# optic_fiber_rx.net
KiCad netlist of a schematic drawn in Altium Designer
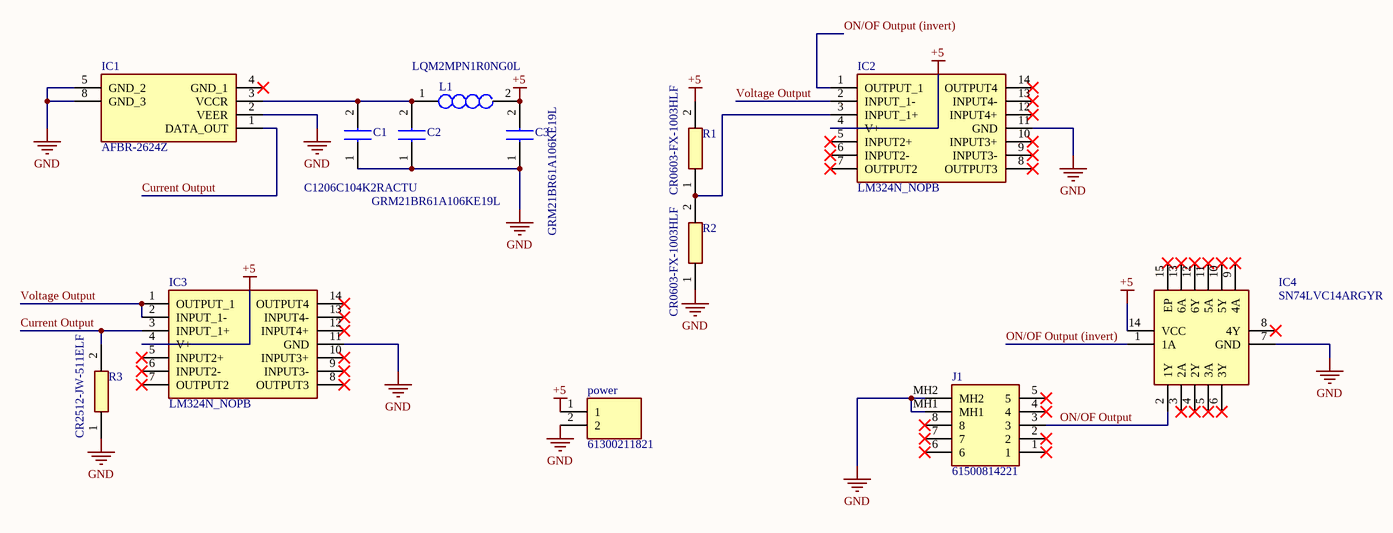
[diagram p0: optic_fiber_rx.SchDoc]

(export (version "E")
  (design (tool "Eeschema 10.0.6"))
  (components
    (comp (ref "C1")
      (value "C1206C104K2RACTU")
      (footprint "optic_fiber:C1206")
      (description "Capacitor")
      (fields (field (name "MOUSER PART NUMBER") "80-C1206C104K2R"))
      (libsource (lib "*") (part "C1206C104K2RACTU"))
    )
    (comp (ref "C2")
      (value "GRM21BR61A106KE19L")
      (footprint "optic_fiber:CAPC2012X145N")
      (description "Capacitor")
      (fields (field (name "MOUSER PART NUMBER") "81-GRM21BR61A106KE19"))
      (libsource (lib "*") (part "GRM21BR61A106KE19L"))
    )
    (comp (ref "C3")
      (value "GRM21BR61A106KE19L")
      (footprint "optic_fiber:CAPC2012X145N")
      (description "Capacitor")
      (fields (field (name "MOUSER PART NUMBER") "81-GRM21BR61A106KE19"))
      (libsource (lib "*") (part "GRM21BR61A106KE19L"))
    )
    (comp (ref "IC1")
      (value "AFBR-2624Z")
      (footprint "optic_fiber:AFBR2624Z")
      (description "Integrated Circuit")
      (fields (field (name "MOUSER PART NUMBER") "630-AFBR-2624Z"))
      (libsource (lib "*") (part "AFBR-2624Z"))
    )
    (comp (ref "IC2")
      (value "LM324N_NOPB")
      (footprint "optic_fiber:DIP794W56P254L1905H533Q14N")
      (description "Integrated Circuit")
      (fields
        (field (name "MANUFACTURER_PART_NUMBER") "LM324N/NOPB")
        (field (name "MOUSER PART NUMBER") "926-LM324N/NOPB")
      )
      (libsource (lib "*") (part "LM324N_NOPB"))
    )
    (comp (ref "IC3")
      (value "LM324N_NOPB")
      (footprint "optic_fiber:DIP794W56P254L1905H533Q14N")
      (description "Integrated Circuit")
      (fields
        (field (name "MANUFACTURER_PART_NUMBER") "LM324N/NOPB")
        (field (name "MOUSER PART NUMBER") "926-LM324N/NOPB")
      )
      (libsource (lib "*") (part "LM324N_NOPB"))
    )
    (comp (ref "IC4")
      (value "SN74LVC14ARGYR")
      (footprint "optic_fiber:RGY-(S-PVQFN-N14)")
      (description "Integrated Circuit")
      (fields (field (name "MOUSER PART NUMBER") "595-SN74LVC14ARGYR"))
      (libsource (lib "*") (part "SN74LVC14ARGYR"))
    )
    (comp (ref "J1")
      (value "61500814221")
      (footprint "optic_fiber:61500814221")
      (description "Connector")
      (fields (field (name "MOUSER PART NUMBER") "710-61500814221"))
      (libsource (lib "*") (part "61500814221"))
    )
    (comp (ref "L1")
      (value "LQM2MPN1R0NG0L")
      (footprint "optic_fiber:LQM2MPN1R0NG0L")
      (description "Inductor")
      (fields (field (name "MOUSER PART NUMBER") "81-LQM2MPN1R0NG0L"))
      (libsource (lib "*") (part "LQM2MPN1R0NG0L"))
    )
    (comp (ref "power")
      (value "61300211821")
      (footprint "optic_fiber:61300211821")
      (description "Connector")
      (libsource (lib "*") (part "61300211821"))
    )
    (comp (ref "R1")
      (value "CR0603-FX-1003HLF")
      (footprint "optic_fiber:RESC1608X55N")
      (description "Resistor")
      (fields (field (name "MOUSER PART NUMBER") "652-CR0603-FX1003HLF"))
      (libsource (lib "*") (part "CR0603-FX-1003HLF"))
    )
    (comp (ref "R2")
      (value "CR0603-FX-1003HLF")
      (footprint "optic_fiber:RESC1608X55N")
      (description "Resistor")
      (fields (field (name "MOUSER PART NUMBER") "652-CR0603-FX1003HLF"))
      (libsource (lib "*") (part "CR0603-FX-1003HLF"))
    )
    (comp (ref "R3")
      (value "CR2512-JW-511ELF")
      (footprint "optic_fiber:RESC6331X75N")
      (description "Resistor")
      (fields (field (name "MOUSER PART NUMBER") "652-CR2512-JW-511ELF"))
      (libsource (lib "*") (part "CR2512-JW-511ELF"))
    )
  )
  (nets
    (net (code "1") (name "+5") (class "Default")
      (node (ref "C3") (pin "2") (pinfunction "2_2") (pintype "passive"))
      (node (ref "IC2") (pin "4") (pinfunction "V+_4") (pintype "passive"))
      (node (ref "IC3") (pin "4") (pinfunction "V+_4") (pintype "passive"))
      (node (ref "IC4") (pin "14") (pinfunction "VCC_14") (pintype "passive"))
      (node (ref "L1") (pin "2") (pinfunction "2_2") (pintype "passive"))
      (node (ref "R1") (pin "2") (pinfunction "2_2") (pintype "passive"))
      (node (ref "power") (pin "1") (pinfunction "1_1") (pintype "passive"))
    )
    (net (code "2") (name "/Current Output") (class "Default")
      (node (ref "IC1") (pin "1") (pinfunction "DATA_OUT_1") (pintype "passive"))
      (node (ref "IC3") (pin "3") (pinfunction "INPUT_1+_3") (pintype "passive"))
      (node (ref "R3") (pin "2") (pinfunction "2_2") (pintype "passive"))
    )
    (net (code "3") (name "/ON{slash}OF Output") (class "Default")
      (node (ref "IC4") (pin "2") (pinfunction "1Y_2") (pintype "passive"))
      (node (ref "J1") (pin "3") (pinfunction "3_3") (pintype "passive"))
    )
    (net (code "4") (name "/ON{slash}OF Output (invert)") (class "Default")
      (node (ref "IC2") (pin "1") (pinfunction "OUTPUT_1_1") (pintype "passive"))
      (node (ref "IC4") (pin "1") (pinfunction "1A_1") (pintype "passive"))
    )
    (net (code "5") (name "/Voltage Output") (class "Default")
      (node (ref "IC2") (pin "2") (pinfunction "INPUT_1-_2") (pintype "passive"))
      (node (ref "IC3") (pin "1") (pinfunction "OUTPUT_1_1") (pintype "passive"))
      (node (ref "IC3") (pin "2") (pinfunction "INPUT_1-_2") (pintype "passive"))
    )
    (net (code "6") (name "GND") (class "Default")
      (node (ref "C1") (pin "1") (pinfunction "1_1") (pintype "passive"))
      (node (ref "C2") (pin "1") (pinfunction "1_1") (pintype "passive"))
      (node (ref "C3") (pin "1") (pinfunction "1_1") (pintype "passive"))
      (node (ref "IC1") (pin "2") (pinfunction "VEER_2") (pintype "passive"))
      (node (ref "IC1") (pin "5") (pinfunction "GND_2_5") (pintype "passive"))
      (node (ref "IC1") (pin "8") (pinfunction "GND_3_8") (pintype "passive"))
      (node (ref "IC2") (pin "11") (pinfunction "GND_11") (pintype "passive"))
      (node (ref "IC3") (pin "11") (pinfunction "GND_11") (pintype "passive"))
      (node (ref "IC4") (pin "7") (pinfunction "GND_7") (pintype "passive"))
      (node (ref "J1") (pin "MH1") (pinfunction "MH1_MH1") (pintype "passive"))
      (node (ref "J1") (pin "MH2") (pinfunction "MH2_MH2") (pintype "passive"))
      (node (ref "R2") (pin "1") (pinfunction "1_1") (pintype "passive"))
      (node (ref "R3") (pin "1") (pinfunction "1_1") (pintype "passive"))
      (node (ref "power") (pin "2") (pinfunction "2_2") (pintype "passive"))
    )
    (net (code "7") (name "Net-(IC1-VCCR)") (class "Default")
      (node (ref "C1") (pin "2") (pinfunction "2_2") (pintype "passive"))
      (node (ref "C2") (pin "2") (pinfunction "2_2") (pintype "passive"))
      (node (ref "IC1") (pin "3") (pinfunction "VCCR_3") (pintype "passive"))
      (node (ref "L1") (pin "1") (pinfunction "1_1") (pintype "passive"))
    )
    (net (code "8") (name "Net-(IC2-INPUT_1+)") (class "Default")
      (node (ref "IC2") (pin "3") (pinfunction "INPUT_1+_3") (pintype "passive"))
      (node (ref "R1") (pin "1") (pinfunction "1_1") (pintype "passive"))
      (node (ref "R2") (pin "2") (pinfunction "2_2") (pintype "passive"))
    )
    (net (code "9") (name "unconnected-(IC1-GND_1-Pad4)") (class "Default")
      (node (ref "IC1") (pin "4") (pinfunction "GND_1_4") (pintype "passive+no_connect"))
    )
    (net (code "10") (name "unconnected-(IC2-INPUT2+-Pad5)") (class "Default")
      (node (ref "IC2") (pin "5") (pinfunction "INPUT2+_5") (pintype "passive+no_connect"))
    )
    (net (code "11") (name "unconnected-(IC2-INPUT2--Pad6)") (class "Default")
      (node (ref "IC2") (pin "6") (pinfunction "INPUT2-_6") (pintype "passive+no_connect"))
    )
    (net (code "12") (name "unconnected-(IC2-INPUT3+-Pad10)") (class "Default")
      (node (ref "IC2") (pin "10") (pinfunction "INPUT3+_10") (pintype "passive+no_connect"))
    )
    (net (code "13") (name "unconnected-(IC2-INPUT3--Pad9)") (class "Default")
      (node (ref "IC2") (pin "9") (pinfunction "INPUT3-_9") (pintype "passive+no_connect"))
    )
    (net (code "14") (name "unconnected-(IC2-INPUT4+-Pad12)") (class "Default")
      (node (ref "IC2") (pin "12") (pinfunction "INPUT4+_12") (pintype "passive+no_connect"))
    )
    (net (code "15") (name "unconnected-(IC2-INPUT4--Pad13)") (class "Default")
      (node (ref "IC2") (pin "13") (pinfunction "INPUT4-_13") (pintype "passive+no_connect"))
    )
    (net (code "16") (name "unconnected-(IC2-OUTPUT2-Pad7)") (class "Default")
      (node (ref "IC2") (pin "7") (pinfunction "OUTPUT2_7") (pintype "passive+no_connect"))
    )
    (net (code "17") (name "unconnected-(IC2-OUTPUT3-Pad8)") (class "Default")
      (node (ref "IC2") (pin "8") (pinfunction "OUTPUT3_8") (pintype "passive+no_connect"))
    )
    (net (code "18") (name "unconnected-(IC2-OUTPUT4-Pad14)") (class "Default")
      (node (ref "IC2") (pin "14") (pinfunction "OUTPUT4_14") (pintype "passive+no_connect"))
    )
    (net (code "19") (name "unconnected-(IC3-INPUT2+-Pad5)") (class "Default")
      (node (ref "IC3") (pin "5") (pinfunction "INPUT2+_5") (pintype "passive+no_connect"))
    )
    (net (code "20") (name "unconnected-(IC3-INPUT2--Pad6)") (class "Default")
      (node (ref "IC3") (pin "6") (pinfunction "INPUT2-_6") (pintype "passive+no_connect"))
    )
    (net (code "21") (name "unconnected-(IC3-INPUT3+-Pad10)") (class "Default")
      (node (ref "IC3") (pin "10") (pinfunction "INPUT3+_10") (pintype "passive+no_connect"))
    )
    (net (code "22") (name "unconnected-(IC3-INPUT3--Pad9)") (class "Default")
      (node (ref "IC3") (pin "9") (pinfunction "INPUT3-_9") (pintype "passive+no_connect"))
    )
    (net (code "23") (name "unconnected-(IC3-INPUT4+-Pad12)") (class "Default")
      (node (ref "IC3") (pin "12") (pinfunction "INPUT4+_12") (pintype "passive+no_connect"))
    )
    (net (code "24") (name "unconnected-(IC3-INPUT4--Pad13)") (class "Default")
      (node (ref "IC3") (pin "13") (pinfunction "INPUT4-_13") (pintype "passive+no_connect"))
    )
    (net (code "25") (name "unconnected-(IC3-OUTPUT2-Pad7)") (class "Default")
      (node (ref "IC3") (pin "7") (pinfunction "OUTPUT2_7") (pintype "passive+no_connect"))
    )
    (net (code "26") (name "unconnected-(IC3-OUTPUT3-Pad8)") (class "Default")
      (node (ref "IC3") (pin "8") (pinfunction "OUTPUT3_8") (pintype "passive+no_connect"))
    )
    (net (code "27") (name "unconnected-(IC3-OUTPUT4-Pad14)") (class "Default")
      (node (ref "IC3") (pin "14") (pinfunction "OUTPUT4_14") (pintype "passive+no_connect"))
    )
    (net (code "28") (name "unconnected-(IC4-2A-Pad3)") (class "Default")
      (node (ref "IC4") (pin "3") (pinfunction "2A_3") (pintype "passive+no_connect"))
    )
    (net (code "29") (name "unconnected-(IC4-2Y-Pad4)") (class "Default")
      (node (ref "IC4") (pin "4") (pinfunction "2Y_4") (pintype "passive+no_connect"))
    )
    (net (code "30") (name "unconnected-(IC4-3A-Pad5)") (class "Default")
      (node (ref "IC4") (pin "5") (pinfunction "3A_5") (pintype "passive+no_connect"))
    )
    (net (code "31") (name "unconnected-(IC4-3Y-Pad6)") (class "Default")
      (node (ref "IC4") (pin "6") (pinfunction "3Y_6") (pintype "passive+no_connect"))
    )
    (net (code "32") (name "unconnected-(IC4-4A-Pad9)") (class "Default")
      (node (ref "IC4") (pin "9") (pinfunction "4A_9") (pintype "passive+no_connect"))
    )
    (net (code "33") (name "unconnected-(IC4-4Y-Pad8)") (class "Default")
      (node (ref "IC4") (pin "8") (pinfunction "4Y_8") (pintype "passive+no_connect"))
    )
    (net (code "34") (name "unconnected-(IC4-5A-Pad11)") (class "Default")
      (node (ref "IC4") (pin "11") (pinfunction "5A_11") (pintype "passive+no_connect"))
    )
    (net (code "35") (name "unconnected-(IC4-5Y-Pad10)") (class "Default")
      (node (ref "IC4") (pin "10") (pinfunction "5Y_10") (pintype "passive+no_connect"))
    )
    (net (code "36") (name "unconnected-(IC4-6A-Pad13)") (class "Default")
      (node (ref "IC4") (pin "13") (pinfunction "6A_13") (pintype "passive+no_connect"))
    )
    (net (code "37") (name "unconnected-(IC4-6Y-Pad12)") (class "Default")
      (node (ref "IC4") (pin "12") (pinfunction "6Y_12") (pintype "passive+no_connect"))
    )
    (net (code "38") (name "unconnected-(IC4-EP-Pad15)") (class "Default")
      (node (ref "IC4") (pin "15") (pinfunction "EP_15") (pintype "passive+no_connect"))
    )
    (net (code "39") (name "unconnected-(J1-Pad1)") (class "Default")
      (node (ref "J1") (pin "1") (pinfunction "1_1") (pintype "passive+no_connect"))
    )
    (net (code "40") (name "unconnected-(J1-Pad2)") (class "Default")
      (node (ref "J1") (pin "2") (pinfunction "2_2") (pintype "passive+no_connect"))
    )
    (net (code "41") (name "unconnected-(J1-Pad4)") (class "Default")
      (node (ref "J1") (pin "4") (pinfunction "4_4") (pintype "passive+no_connect"))
    )
    (net (code "42") (name "unconnected-(J1-Pad5)") (class "Default")
      (node (ref "J1") (pin "5") (pinfunction "5_5") (pintype "passive+no_connect"))
    )
    (net (code "43") (name "unconnected-(J1-Pad6)") (class "Default")
      (node (ref "J1") (pin "6") (pinfunction "6_6") (pintype "passive+no_connect"))
    )
    (net (code "44") (name "unconnected-(J1-Pad7)") (class "Default")
      (node (ref "J1") (pin "7") (pinfunction "7_7") (pintype "passive+no_connect"))
    )
    (net (code "45") (name "unconnected-(J1-Pad8)") (class "Default")
      (node (ref "J1") (pin "8") (pinfunction "8_8") (pintype "passive+no_connect"))
    )
  )
)
